# IO_Carte_Nucleo.net
KiCad netlist of a schematic drawn in Altium Designer
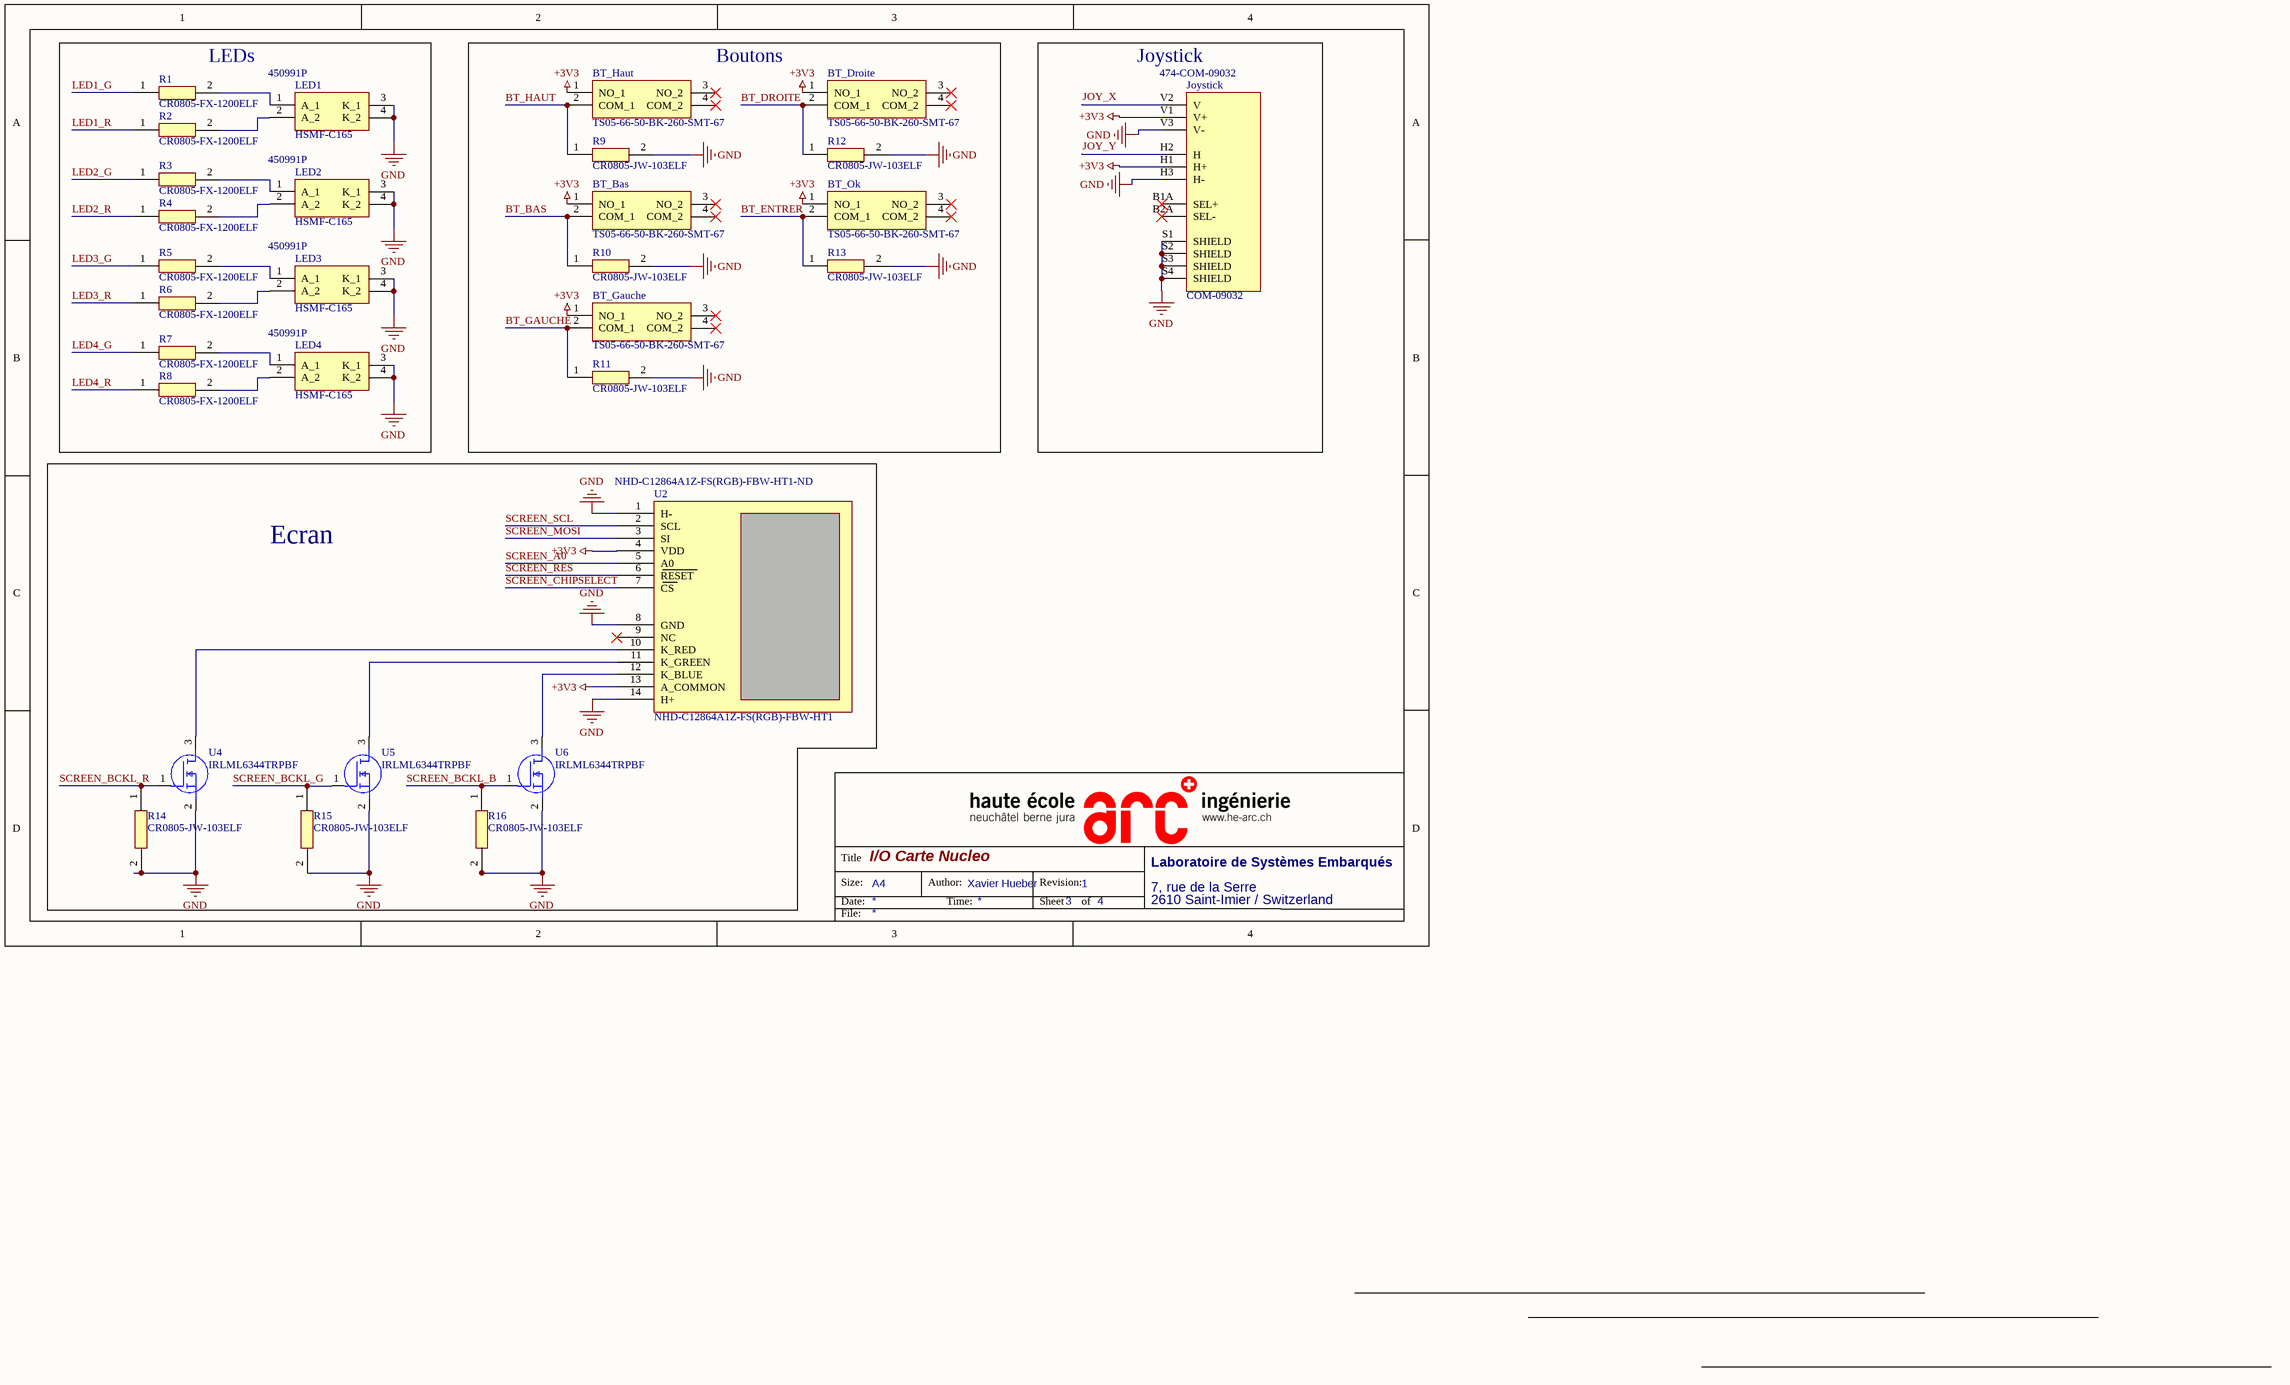
[diagram p0: IO_Carte_Nucleo_.SchDoc]

(export (version "E")
  (design (tool "Eeschema 10.0.6"))
  (components
    (comp (ref "BT_Bas")
      (value "TS05-66-50-BK-260-SMT-67")
      (footprint "SamacSys:TS056650BK260SMT67")
      (description "6 x 6 mm, 4.3 ~ 8 mm Actuator Height, 100 ~ 260 gf, Surface Mount, IP67, SPST, Tactile Switch")
      (libsource (lib "*") (part "TS05-66-50-BK-260-SMT-67"))
    )
    (comp (ref "BT_Droite")
      (value "TS05-66-50-BK-260-SMT-67")
      (footprint "SamacSys:TS056650BK260SMT67")
      (description "6 x 6 mm, 4.3 ~ 8 mm Actuator Height, 100 ~ 260 gf, Surface Mount, IP67, SPST, Tactile Switch")
      (libsource (lib "*") (part "TS05-66-50-BK-260-SMT-67"))
    )
    (comp (ref "BT_Gauche")
      (value "TS05-66-50-BK-260-SMT-67")
      (footprint "SamacSys:TS056650BK260SMT67")
      (description "6 x 6 mm, 4.3 ~ 8 mm Actuator Height, 100 ~ 260 gf, Surface Mount, IP67, SPST, Tactile Switch")
      (libsource (lib "*") (part "TS05-66-50-BK-260-SMT-67"))
    )
    (comp (ref "BT_Haut")
      (value "TS05-66-50-BK-260-SMT-67")
      (footprint "SamacSys:TS056650BK260SMT67")
      (description "6 x 6 mm, 4.3 ~ 8 mm Actuator Height, 100 ~ 260 gf, Surface Mount, IP67, SPST, Tactile Switch")
      (libsource (lib "*") (part "TS05-66-50-BK-260-SMT-67"))
    )
    (comp (ref "BT_Ok")
      (value "TS05-66-50-BK-260-SMT-67")
      (footprint "SamacSys:TS056650BK260SMT67")
      (description "6 x 6 mm, 4.3 ~ 8 mm Actuator Height, 100 ~ 260 gf, Surface Mount, IP67, SPST, Tactile Switch")
      (libsource (lib "*") (part "TS05-66-50-BK-260-SMT-67"))
    )
    (comp (ref "Joystick")
      (value "COM-09032")
      (footprint "XDCR_COM-09032")
      (description "Thumb Joystick")
      (fields (field (name "SUPPLIER PART NUMBER 1") "474-COM-09032"))
      (libsource (lib "COM-09032") (part "COM-09032"))
    )
    (comp (ref "LED1")
      (value "HSMF-C165")
      (footprint "SamacSys:HSMF-C163")
      (description "Standard LEDs - SMD Grn/Red Bi-Color")
      (fields
        (field (name "MOUSER2 PART NUMBER") "630-HSMF-C165")
        (field (name "SUPPLIER PART NUMBER 1") "450991P")
      )
      (libsource (lib "*") (part "HSMF-C165"))
    )
    (comp (ref "LED2")
      (value "HSMF-C165")
      (footprint "SamacSys:HSMF-C163")
      (description "Standard LEDs - SMD Grn/Red Bi-Color")
      (fields
        (field (name "MOUSER2 PART NUMBER") "630-HSMF-C165")
        (field (name "SUPPLIER PART NUMBER 1") "450991P")
      )
      (libsource (lib "*") (part "HSMF-C165"))
    )
    (comp (ref "LED3")
      (value "HSMF-C165")
      (footprint "SamacSys:HSMF-C163")
      (description "Standard LEDs - SMD Grn/Red Bi-Color")
      (fields
        (field (name "MOUSER2 PART NUMBER") "630-HSMF-C165")
        (field (name "SUPPLIER PART NUMBER 1") "450991P")
      )
      (libsource (lib "*") (part "HSMF-C165"))
    )
    (comp (ref "LED4")
      (value "HSMF-C165")
      (footprint "SamacSys:HSMF-C163")
      (description "Standard LEDs - SMD Grn/Red Bi-Color")
      (fields
        (field (name "MOUSER2 PART NUMBER") "630-HSMF-C165")
        (field (name "SUPPLIER PART NUMBER 1") "450991P")
      )
      (libsource (lib "*") (part "HSMF-C165"))
    )
    (comp (ref "R1")
      (value "CR0805-FX-1200ELF")
      (footprint "SamacSys:RESC2012X60N")
      (description "Res Thick Film 0805 120 Ohm 1% 1/8W ±100ppm/°C Molded SMD SMD Paper Tape on Plastic Reel")
      (libsource (lib "*") (part "CR0805-FX-1200ELF"))
    )
    (comp (ref "R2")
      (value "CR0805-FX-1200ELF")
      (footprint "SamacSys:RESC2012X60N")
      (description "Res Thick Film 0805 120 Ohm 1% 1/8W ±100ppm/°C Molded SMD SMD Paper Tape on Plastic Reel")
      (libsource (lib "*") (part "CR0805-FX-1200ELF"))
    )
    (comp (ref "R3")
      (value "CR0805-FX-1200ELF")
      (footprint "SamacSys:RESC2012X60N")
      (description "Res Thick Film 0805 120 Ohm 1% 1/8W ±100ppm/°C Molded SMD SMD Paper Tape on Plastic Reel")
      (libsource (lib "*") (part "CR0805-FX-1200ELF"))
    )
    (comp (ref "R4")
      (value "CR0805-FX-1200ELF")
      (footprint "SamacSys:RESC2012X60N")
      (description "Res Thick Film 0805 120 Ohm 1% 1/8W ±100ppm/°C Molded SMD SMD Paper Tape on Plastic Reel")
      (libsource (lib "*") (part "CR0805-FX-1200ELF"))
    )
    (comp (ref "R5")
      (value "CR0805-FX-1200ELF")
      (footprint "SamacSys:RESC2012X60N")
      (description "Res Thick Film 0805 120 Ohm 1% 1/8W ±100ppm/°C Molded SMD SMD Paper Tape on Plastic Reel")
      (libsource (lib "*") (part "CR0805-FX-1200ELF"))
    )
    (comp (ref "R6")
      (value "CR0805-FX-1200ELF")
      (footprint "SamacSys:RESC2012X60N")
      (description "Res Thick Film 0805 120 Ohm 1% 1/8W ±100ppm/°C Molded SMD SMD Paper Tape on Plastic Reel")
      (libsource (lib "*") (part "CR0805-FX-1200ELF"))
    )
    (comp (ref "R7")
      (value "CR0805-FX-1200ELF")
      (footprint "SamacSys:RESC2012X60N")
      (description "Res Thick Film 0805 120 Ohm 1% 1/8W ±100ppm/°C Molded SMD SMD Paper Tape on Plastic Reel")
      (libsource (lib "*") (part "CR0805-FX-1200ELF"))
    )
    (comp (ref "R8")
      (value "CR0805-FX-1200ELF")
      (footprint "SamacSys:RESC2012X60N")
      (description "Res Thick Film 0805 120 Ohm 1% 1/8W ±100ppm/°C Molded SMD SMD Paper Tape on Plastic Reel")
      (libsource (lib "*") (part "CR0805-FX-1200ELF"))
    )
    (comp (ref "R9")
      (value "CR0805-JW-103ELF")
      (footprint "SamacSys:RESC2012X60N")
      (libsource (lib "*") (part "CR0805-JW-103ELF"))
    )
    (comp (ref "R10")
      (value "CR0805-JW-103ELF")
      (footprint "SamacSys:RESC2012X60N")
      (libsource (lib "*") (part "CR0805-JW-103ELF"))
    )
    (comp (ref "R11")
      (value "CR0805-JW-103ELF")
      (footprint "SamacSys:RESC2012X60N")
      (libsource (lib "*") (part "CR0805-JW-103ELF"))
    )
    (comp (ref "R12")
      (value "CR0805-JW-103ELF")
      (footprint "SamacSys:RESC2012X60N")
      (libsource (lib "*") (part "CR0805-JW-103ELF"))
    )
    (comp (ref "R13")
      (value "CR0805-JW-103ELF")
      (footprint "SamacSys:RESC2012X60N")
      (libsource (lib "*") (part "CR0805-JW-103ELF"))
    )
    (comp (ref "R14")
      (value "CR0805-JW-103ELF")
      (footprint "SamacSys:RESC2012X60N")
      (libsource (lib "") (part "CR0805-JW-103ELF_1"))
    )
    (comp (ref "R15")
      (value "CR0805-JW-103ELF")
      (footprint "SamacSys:RESC2012X60N")
      (libsource (lib "") (part "CR0805-JW-103ELF_1"))
    )
    (comp (ref "R16")
      (value "CR0805-JW-103ELF")
      (footprint "SamacSys:RESC2012X60N")
      (libsource (lib "") (part "CR0805-JW-103ELF_1"))
    )
    (comp (ref "U2")
      (value "NHD-C12864A1Z-FS(RGB)-FBW-HT1")
      (footprint "NHD-C12864A1Z-FS(RGB)-FBW-HT1")
      (description "LCD COG GRAPH 128X64 RGB BKLT")
      (fields (field (name "SUPPLIER PART NUMBER 1") "NHD-C12864A1Z-FS(RGB)-FBW-HT1-ND"))
      (libsource (lib "MesComposants") (part "NHD-C12864A1Z-FS(RGB)-FBW-HT1"))
    )
    (comp (ref "U4")
      (value "IRLML6344TRPBF")
      (footprint "SamacSys:SOT95P237X112-3N")
      (description "MOSFET (N-Channel)")
      (fields (field (name "MOUSER2 PART NUMBER") "942-IRLML6344TRPBF"))
      (libsource (lib "*") (part "IRLML6344TRPBF"))
    )
    (comp (ref "U5")
      (value "IRLML6344TRPBF")
      (footprint "SamacSys:SOT95P237X112-3N")
      (description "MOSFET (N-Channel)")
      (fields (field (name "MOUSER2 PART NUMBER") "942-IRLML6344TRPBF"))
      (libsource (lib "*") (part "IRLML6344TRPBF"))
    )
    (comp (ref "U6")
      (value "IRLML6344TRPBF")
      (footprint "SamacSys:SOT95P237X112-3N")
      (description "MOSFET (N-Channel)")
      (fields (field (name "MOUSER2 PART NUMBER") "942-IRLML6344TRPBF"))
      (libsource (lib "*") (part "IRLML6344TRPBF"))
    )
  )
  (nets
    (net (code "1") (name "+3V3") (class "Default")
      (node (ref "BT_Bas") (pin "1") (pinfunction "NO_1_1") (pintype "passive"))
      (node (ref "BT_Droite") (pin "1") (pinfunction "NO_1_1") (pintype "passive"))
      (node (ref "BT_Gauche") (pin "1") (pinfunction "NO_1_1") (pintype "passive"))
      (node (ref "BT_Haut") (pin "1") (pinfunction "NO_1_1") (pintype "passive"))
      (node (ref "BT_Ok") (pin "1") (pinfunction "NO_1_1") (pintype "passive"))
      (node (ref "Joystick") (pin "H1") (pinfunction "H+_H1") (pintype "passive"))
      (node (ref "Joystick") (pin "V1") (pinfunction "V+_V1") (pintype "passive"))
      (node (ref "U2") (pin "13") (pinfunction "A_COMMON_13") (pintype "passive"))
      (node (ref "U2") (pin "4") (pinfunction "VDD_4") (pintype "passive"))
    )
    (net (code "2") (name "/BT_BAS") (class "Default")
      (node (ref "BT_Bas") (pin "2") (pinfunction "COM_1_2") (pintype "passive"))
      (node (ref "R10") (pin "1") (pinfunction "1_1") (pintype "passive"))
    )
    (net (code "3") (name "/BT_DROITE") (class "Default")
      (node (ref "BT_Droite") (pin "2") (pinfunction "COM_1_2") (pintype "passive"))
      (node (ref "R12") (pin "1") (pinfunction "1_1") (pintype "passive"))
    )
    (net (code "4") (name "/BT_ENTRER") (class "Default")
      (node (ref "BT_Ok") (pin "2") (pinfunction "COM_1_2") (pintype "passive"))
      (node (ref "R13") (pin "1") (pinfunction "1_1") (pintype "passive"))
    )
    (net (code "5") (name "/BT_GAUCHE") (class "Default")
      (node (ref "BT_Gauche") (pin "2") (pinfunction "COM_1_2") (pintype "passive"))
      (node (ref "R11") (pin "1") (pinfunction "1_1") (pintype "passive"))
    )
    (net (code "6") (name "/BT_HAUT") (class "Default")
      (node (ref "BT_Haut") (pin "2") (pinfunction "COM_1_2") (pintype "passive"))
      (node (ref "R9") (pin "1") (pinfunction "1_1") (pintype "passive"))
    )
    (net (code "7") (name "/JOY_X") (class "Default")
      (node (ref "Joystick") (pin "V2") (pinfunction "V_V2") (pintype "passive"))
    )
    (net (code "8") (name "/JOY_Y") (class "Default")
      (node (ref "Joystick") (pin "H2") (pinfunction "H_H2") (pintype "passive"))
    )
    (net (code "9") (name "/LED1_G") (class "Default")
      (node (ref "R1") (pin "1") (pinfunction "1_1") (pintype "passive"))
    )
    (net (code "10") (name "/LED1_R") (class "Default")
      (node (ref "R2") (pin "1") (pinfunction "1_1") (pintype "passive"))
    )
    (net (code "11") (name "/LED2_G") (class "Default")
      (node (ref "R3") (pin "1") (pinfunction "1_1") (pintype "passive"))
    )
    (net (code "12") (name "/LED2_R") (class "Default")
      (node (ref "R4") (pin "1") (pinfunction "1_1") (pintype "passive"))
    )
    (net (code "13") (name "/LED3_G") (class "Default")
      (node (ref "R5") (pin "1") (pinfunction "1_1") (pintype "passive"))
    )
    (net (code "14") (name "/LED3_R") (class "Default")
      (node (ref "R6") (pin "1") (pinfunction "1_1") (pintype "passive"))
    )
    (net (code "15") (name "/LED4_G") (class "Default")
      (node (ref "R7") (pin "1") (pinfunction "1_1") (pintype "passive"))
    )
    (net (code "16") (name "/LED4_R") (class "Default")
      (node (ref "R8") (pin "1") (pinfunction "1_1") (pintype "passive"))
    )
    (net (code "17") (name "/SCREEN_A0") (class "Default")
      (node (ref "U2") (pin "5") (pinfunction "A0_5") (pintype "passive"))
    )
    (net (code "18") (name "/SCREEN_BCKL_B") (class "Default")
      (node (ref "R16") (pin "1") (pinfunction "1_1") (pintype "passive"))
      (node (ref "U6") (pin "1") (pinfunction "G_1") (pintype "passive"))
    )
    (net (code "19") (name "/SCREEN_BCKL_G") (class "Default")
      (node (ref "R15") (pin "1") (pinfunction "1_1") (pintype "passive"))
      (node (ref "U5") (pin "1") (pinfunction "G_1") (pintype "passive"))
    )
    (net (code "20") (name "/SCREEN_BCKL_R") (class "Default")
      (node (ref "R14") (pin "1") (pinfunction "1_1") (pintype "passive"))
      (node (ref "U4") (pin "1") (pinfunction "G_1") (pintype "passive"))
    )
    (net (code "21") (name "/SCREEN_CHIPSELECT") (class "Default")
      (node (ref "U2") (pin "7") (pinfunction "CS_7") (pintype "passive"))
    )
    (net (code "22") (name "/SCREEN_MOSI") (class "Default")
      (node (ref "U2") (pin "3") (pinfunction "SI_3") (pintype "passive"))
    )
    (net (code "23") (name "/SCREEN_RES") (class "Default")
      (node (ref "U2") (pin "6") (pinfunction "RESET_6") (pintype "passive"))
    )
    (net (code "24") (name "/SCREEN_SCL") (class "Default")
      (node (ref "U2") (pin "2") (pinfunction "SCL_2") (pintype "passive"))
    )
    (net (code "25") (name "GND") (class "Default")
      (node (ref "Joystick") (pin "H3") (pinfunction "H-_H3") (pintype "passive"))
      (node (ref "Joystick") (pin "S1") (pinfunction "SHIELD_S1") (pintype "passive"))
      (node (ref "Joystick") (pin "S2") (pinfunction "SHIELD_S2") (pintype "passive"))
      (node (ref "Joystick") (pin "S3") (pinfunction "SHIELD_S3") (pintype "passive"))
      (node (ref "Joystick") (pin "S4") (pinfunction "SHIELD_S4") (pintype "passive"))
      (node (ref "Joystick") (pin "V3") (pinfunction "V-_V3") (pintype "passive"))
      (node (ref "LED1") (pin "3") (pinfunction "K_1_3") (pintype "passive"))
      (node (ref "LED1") (pin "4") (pinfunction "K_2_4") (pintype "passive"))
      (node (ref "LED2") (pin "3") (pinfunction "K_1_3") (pintype "passive"))
      (node (ref "LED2") (pin "4") (pinfunction "K_2_4") (pintype "passive"))
      (node (ref "LED3") (pin "3") (pinfunction "K_1_3") (pintype "passive"))
      (node (ref "LED3") (pin "4") (pinfunction "K_2_4") (pintype "passive"))
      (node (ref "LED4") (pin "3") (pinfunction "K_1_3") (pintype "passive"))
      (node (ref "LED4") (pin "4") (pinfunction "K_2_4") (pintype "passive"))
      (node (ref "R10") (pin "2") (pinfunction "2_2") (pintype "passive"))
      (node (ref "R11") (pin "2") (pinfunction "2_2") (pintype "passive"))
      (node (ref "R12") (pin "2") (pinfunction "2_2") (pintype "passive"))
      (node (ref "R13") (pin "2") (pinfunction "2_2") (pintype "passive"))
      (node (ref "R14") (pin "2") (pinfunction "2_2") (pintype "passive"))
      (node (ref "R15") (pin "2") (pinfunction "2_2") (pintype "passive"))
      (node (ref "R16") (pin "2") (pinfunction "2_2") (pintype "passive"))
      (node (ref "R9") (pin "2") (pinfunction "2_2") (pintype "passive"))
      (node (ref "U2") (pin "1") (pinfunction "H-_1") (pintype "passive"))
      (node (ref "U2") (pin "14") (pinfunction "H+_14") (pintype "passive"))
      (node (ref "U2") (pin "8") (pinfunction "GND_8") (pintype "passive"))
      (node (ref "U4") (pin "2") (pinfunction "S_2") (pintype "passive"))
      (node (ref "U5") (pin "2") (pinfunction "S_2") (pintype "passive"))
      (node (ref "U6") (pin "2") (pinfunction "S_2") (pintype "passive"))
    )
    (net (code "26") (name "Net-(LED1-A_1)") (class "Default")
      (node (ref "LED1") (pin "1") (pinfunction "A_1_1") (pintype "passive"))
      (node (ref "R1") (pin "2") (pinfunction "2_2") (pintype "passive"))
    )
    (net (code "27") (name "Net-(LED1-A_2)") (class "Default")
      (node (ref "LED1") (pin "2") (pinfunction "A_2_2") (pintype "passive"))
      (node (ref "R2") (pin "2") (pinfunction "2_2") (pintype "passive"))
    )
    (net (code "28") (name "Net-(LED2-A_1)") (class "Default")
      (node (ref "LED2") (pin "1") (pinfunction "A_1_1") (pintype "passive"))
      (node (ref "R3") (pin "2") (pinfunction "2_2") (pintype "passive"))
    )
    (net (code "29") (name "Net-(LED2-A_2)") (class "Default")
      (node (ref "LED2") (pin "2") (pinfunction "A_2_2") (pintype "passive"))
      (node (ref "R4") (pin "2") (pinfunction "2_2") (pintype "passive"))
    )
    (net (code "30") (name "Net-(LED3-A_1)") (class "Default")
      (node (ref "LED3") (pin "1") (pinfunction "A_1_1") (pintype "passive"))
      (node (ref "R5") (pin "2") (pinfunction "2_2") (pintype "passive"))
    )
    (net (code "31") (name "Net-(LED3-A_2)") (class "Default")
      (node (ref "LED3") (pin "2") (pinfunction "A_2_2") (pintype "passive"))
      (node (ref "R6") (pin "2") (pinfunction "2_2") (pintype "passive"))
    )
    (net (code "32") (name "Net-(LED4-A_1)") (class "Default")
      (node (ref "LED4") (pin "1") (pinfunction "A_1_1") (pintype "passive"))
      (node (ref "R7") (pin "2") (pinfunction "2_2") (pintype "passive"))
    )
    (net (code "33") (name "Net-(LED4-A_2)") (class "Default")
      (node (ref "LED4") (pin "2") (pinfunction "A_2_2") (pintype "passive"))
      (node (ref "R8") (pin "2") (pinfunction "2_2") (pintype "passive"))
    )
    (net (code "34") (name "Net-(U2-K_BLUE)") (class "Default")
      (node (ref "U2") (pin "12") (pinfunction "K_BLUE_12") (pintype "passive"))
      (node (ref "U6") (pin "3") (pinfunction "D_3") (pintype "passive"))
    )
    (net (code "35") (name "Net-(U2-K_GREEN)") (class "Default")
      (node (ref "U2") (pin "11") (pinfunction "K_GREEN_11") (pintype "passive"))
      (node (ref "U5") (pin "3") (pinfunction "D_3") (pintype "passive"))
    )
    (net (code "36") (name "Net-(U2-K_RED)") (class "Default")
      (node (ref "U2") (pin "10") (pinfunction "K_RED_10") (pintype "passive"))
      (node (ref "U4") (pin "3") (pinfunction "D_3") (pintype "passive"))
    )
    (net (code "37") (name "unconnected-(BT_Bas-COM_2-Pad4)") (class "Default")
      (node (ref "BT_Bas") (pin "4") (pinfunction "COM_2_4") (pintype "passive+no_connect"))
    )
    (net (code "38") (name "unconnected-(BT_Bas-NO_2-Pad3)") (class "Default")
      (node (ref "BT_Bas") (pin "3") (pinfunction "NO_2_3") (pintype "passive+no_connect"))
    )
    (net (code "39") (name "unconnected-(BT_Droite-COM_2-Pad4)") (class "Default")
      (node (ref "BT_Droite") (pin "4") (pinfunction "COM_2_4") (pintype "passive+no_connect"))
    )
    (net (code "40") (name "unconnected-(BT_Droite-NO_2-Pad3)") (class "Default")
      (node (ref "BT_Droite") (pin "3") (pinfunction "NO_2_3") (pintype "passive+no_connect"))
    )
    (net (code "41") (name "unconnected-(BT_Gauche-COM_2-Pad4)") (class "Default")
      (node (ref "BT_Gauche") (pin "4") (pinfunction "COM_2_4") (pintype "passive+no_connect"))
    )
    (net (code "42") (name "unconnected-(BT_Gauche-NO_2-Pad3)") (class "Default")
      (node (ref "BT_Gauche") (pin "3") (pinfunction "NO_2_3") (pintype "passive+no_connect"))
    )
    (net (code "43") (name "unconnected-(BT_Haut-COM_2-Pad4)") (class "Default")
      (node (ref "BT_Haut") (pin "4") (pinfunction "COM_2_4") (pintype "passive+no_connect"))
    )
    (net (code "44") (name "unconnected-(BT_Haut-NO_2-Pad3)") (class "Default")
      (node (ref "BT_Haut") (pin "3") (pinfunction "NO_2_3") (pintype "passive+no_connect"))
    )
    (net (code "45") (name "unconnected-(BT_Ok-COM_2-Pad4)") (class "Default")
      (node (ref "BT_Ok") (pin "4") (pinfunction "COM_2_4") (pintype "passive+no_connect"))
    )
    (net (code "46") (name "unconnected-(BT_Ok-NO_2-Pad3)") (class "Default")
      (node (ref "BT_Ok") (pin "3") (pinfunction "NO_2_3") (pintype "passive+no_connect"))
    )
    (net (code "47") (name "unconnected-(Joystick-SEL+-PadB1A)") (class "Default")
      (node (ref "Joystick") (pin "B1A") (pinfunction "SEL+_B1A") (pintype "passive+no_connect"))
    )
    (net (code "48") (name "unconnected-(Joystick-SEL--PadB2A)") (class "Default")
      (node (ref "Joystick") (pin "B2A") (pinfunction "SEL-_B2A") (pintype "passive+no_connect"))
    )
    (net (code "49") (name "unconnected-(U2-NC-Pad9)") (class "Default")
      (node (ref "U2") (pin "9") (pinfunction "NC_9") (pintype "passive+no_connect"))
    )
  )
)
